# AntennaBoard.net
KiCad netlist of a schematic drawn in EAGLE
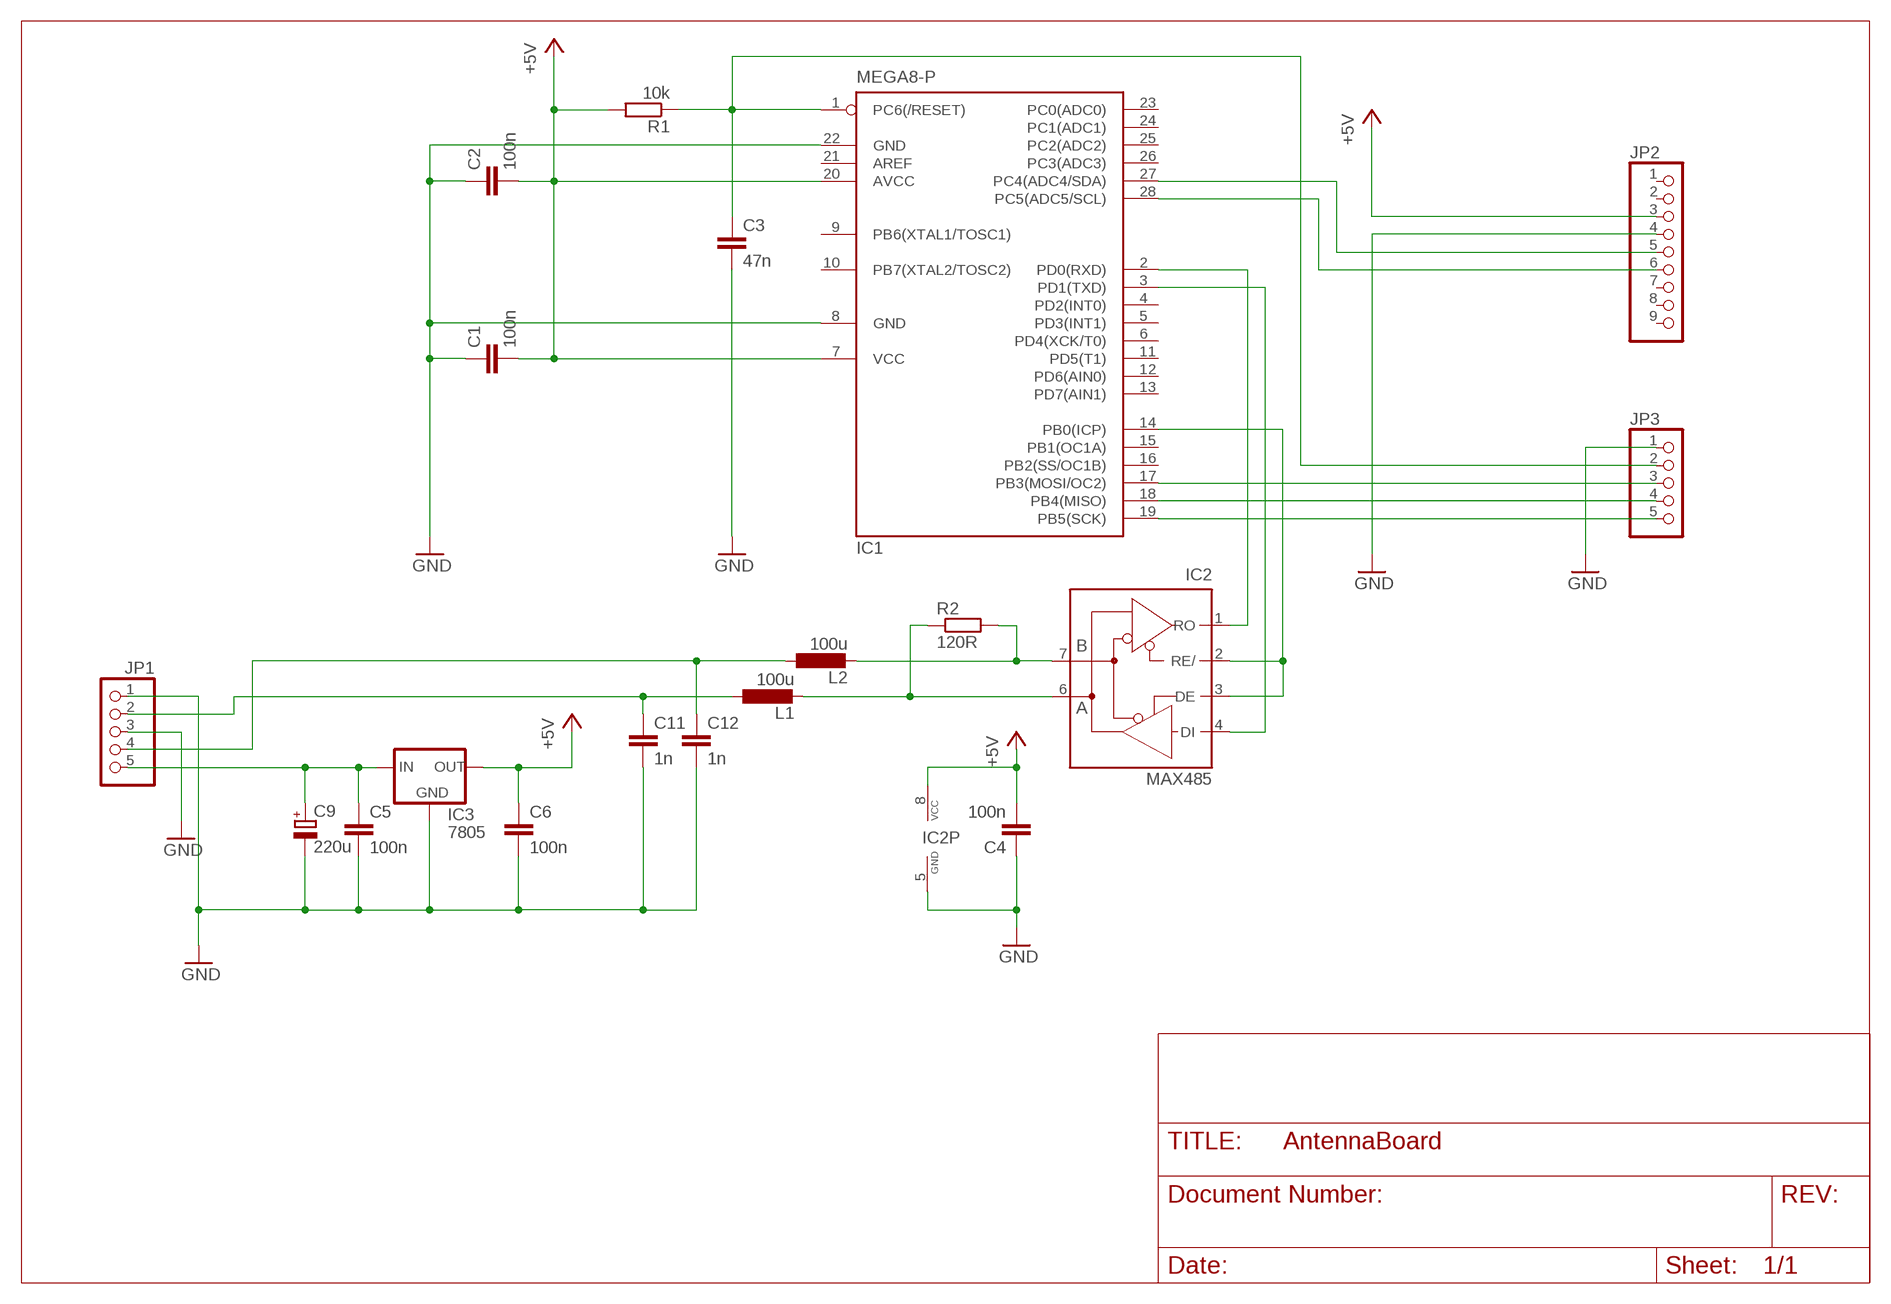
[diagram p0: schematic, sheet 1]

(export (version "E")
  (design (tool "Eeschema 10.0.6"))
  (components
    (comp (ref "C1")
      (value "100n")
      (footprint "eagle-import:C050-024X044")
      (libsource (lib "eagle-import") (part "C-EU050-024X044"))
    )
    (comp (ref "C2")
      (value "100n")
      (footprint "eagle-import:C050-024X044")
      (libsource (lib "eagle-import") (part "C-EU050-024X044"))
    )
    (comp (ref "C3")
      (value "47n")
      (footprint "eagle-import:C050-024X044")
      (libsource (lib "eagle-import") (part "C-EU050-024X044"))
    )
    (comp (ref "C4")
      (value "100n")
      (footprint "eagle-import:C050-024X044")
      (libsource (lib "eagle-import") (part "C-EU050-024X044"))
    )
    (comp (ref "C5")
      (value "100n")
      (footprint "eagle-import:C050-024X044")
      (libsource (lib "eagle-import") (part "C-EU050-024X044"))
    )
    (comp (ref "C6")
      (value "100n")
      (footprint "eagle-import:C050-024X044")
      (libsource (lib "eagle-import") (part "C-EU050-024X044"))
    )
    (comp (ref "C9")
      (value "220u")
      (footprint "eagle-import:E5-10,5")
      (libsource (lib "eagle-import") (part "CPOL-EUE5-10.5"))
    )
    (comp (ref "C11")
      (value "1n")
      (footprint "eagle-import:C025-024X044")
      (libsource (lib "eagle-import") (part "C-EU025-024X044"))
    )
    (comp (ref "C12")
      (value "1n")
      (footprint "eagle-import:C025-024X044")
      (libsource (lib "eagle-import") (part "C-EU025-024X044"))
    )
    (comp (ref "IC1")
      (value "MEGA8-P")
      (footprint "eagle-import:DIL28-3")
      (libsource (lib "eagle-import") (part "MEGA8-P"))
    )
    (comp (ref "IC2")
      (value "MAX485")
      (footprint "eagle-import:DIL08")
      (fields (field (name "MPN") "MAX481CPA+"))
      (libsource (lib "eagle-import") (part "MAX481CPA"))
    )
    (comp (ref "IC3")
      (value "7805")
      (footprint "eagle-import:78XXL")
      (libsource (lib "eagle-import") (part "78XXL"))
    )
    (comp (ref "JP1")
      (value "PINHD-1X5/90")
      (footprint "eagle-import:1X05_90")
      (libsource (lib "eagle-import") (part "PINHD-1X5/90"))
    )
    (comp (ref "JP2")
      (value "PINHD-1X9")
      (footprint "eagle-import:1X09")
      (libsource (lib "eagle-import") (part "PINHD-1X9"))
    )
    (comp (ref "JP3")
      (value "PINHD-1X5")
      (footprint "eagle-import:1X05")
      (libsource (lib "eagle-import") (part "PINHD-1X5"))
    )
    (comp (ref "L1")
      (value "100u")
      (footprint "eagle-import:0207_12")
      (libsource (lib "eagle-import") (part "L-EU0207/12"))
    )
    (comp (ref "L2")
      (value "100u")
      (footprint "eagle-import:0207_12")
      (libsource (lib "eagle-import") (part "L-EU0207/12"))
    )
    (comp (ref "R1")
      (value "10k")
      (footprint "eagle-import:0207_10")
      (libsource (lib "eagle-import") (part "R-EU_0207/10"))
    )
    (comp (ref "R2")
      (value "120R")
      (footprint "eagle-import:0207_10")
      (libsource (lib "eagle-import") (part "R-EU_0207/10"))
    )
  )
  (nets
    (net (code "1") (name "+5V") (class "Default")
      (node (ref "C1") (pin "2") (pinfunction "2_2") (pintype "passive"))
      (node (ref "C2") (pin "2") (pinfunction "2_2") (pintype "passive"))
      (node (ref "C4") (pin "2") (pinfunction "2_2") (pintype "passive"))
      (node (ref "C6") (pin "1") (pinfunction "1_1") (pintype "passive"))
      (node (ref "IC1") (pin "20") (pinfunction "AVCC_20") (pintype "power_in"))
      (node (ref "IC1") (pin "7") (pinfunction "VCC_7") (pintype "power_in"))
      (node (ref "IC2") (pin "8") (pinfunction "VCC_8") (pintype "power_in"))
      (node (ref "IC3") (pin "OUT") (pinfunction "OUT_OUT") (pintype "passive"))
      (node (ref "JP2") (pin "3") (pinfunction "3_3") (pintype "passive"))
      (node (ref "R1") (pin "2") (pinfunction "2_2") (pintype "passive"))
    )
    (net (code "2") (name "GND") (class "Default")
      (node (ref "C1") (pin "1") (pinfunction "1_1") (pintype "passive"))
      (node (ref "C11") (pin "2") (pinfunction "2_2") (pintype "passive"))
      (node (ref "C12") (pin "2") (pinfunction "2_2") (pintype "passive"))
      (node (ref "C2") (pin "1") (pinfunction "1_1") (pintype "passive"))
      (node (ref "C3") (pin "2") (pinfunction "2_2") (pintype "passive"))
      (node (ref "C4") (pin "1") (pinfunction "1_1") (pintype "passive"))
      (node (ref "C5") (pin "2") (pinfunction "2_2") (pintype "passive"))
      (node (ref "C6") (pin "2") (pinfunction "2_2") (pintype "passive"))
      (node (ref "C9") (pin "-") (pinfunction "-_-") (pintype "passive"))
      (node (ref "IC1") (pin "22") (pinfunction "GND_22") (pintype "power_in"))
      (node (ref "IC1") (pin "8") (pinfunction "GND_8") (pintype "power_in"))
      (node (ref "IC2") (pin "5") (pinfunction "GND_5") (pintype "power_in"))
      (node (ref "IC3") (pin "GND") (pinfunction "GND_GND") (pintype "input"))
      (node (ref "JP1") (pin "1") (pinfunction "1_1") (pintype "passive"))
      (node (ref "JP1") (pin "3") (pinfunction "3_3") (pintype "passive"))
      (node (ref "JP2") (pin "4") (pinfunction "4_4") (pintype "passive"))
      (node (ref "JP3") (pin "1") (pinfunction "1_1") (pintype "passive"))
    )
    (net (code "3") (name "Net-(C5-Pad1)") (class "Default")
      (node (ref "C5") (pin "1") (pinfunction "1_1") (pintype "passive"))
      (node (ref "C9") (pin "+") (pinfunction "+_+") (pintype "passive"))
      (node (ref "IC3") (pin "IN") (pinfunction "IN_IN") (pintype "input"))
      (node (ref "JP1") (pin "5") (pinfunction "5_5") (pintype "passive"))
    )
    (net (code "4") (name "Net-(C11-Pad1)") (class "Default")
      (node (ref "C11") (pin "1") (pinfunction "1_1") (pintype "passive"))
      (node (ref "JP1") (pin "2") (pinfunction "2_2") (pintype "passive"))
      (node (ref "L1") (pin "1") (pinfunction "1_1") (pintype "passive"))
    )
    (net (code "5") (name "Net-(C12-Pad1)") (class "Default")
      (node (ref "C12") (pin "1") (pinfunction "1_1") (pintype "passive"))
      (node (ref "JP1") (pin "4") (pinfunction "4_4") (pintype "passive"))
      (node (ref "L2") (pin "1") (pinfunction "1_1") (pintype "passive"))
    )
    (net (code "6") (name "Net-(IC1-PB0(ICP))") (class "Default")
      (node (ref "IC1") (pin "14") (pinfunction "PB0(ICP)_14") (pintype "bidirectional"))
      (node (ref "IC2") (pin "2") (pinfunction "RE/_2") (pintype "input"))
      (node (ref "IC2") (pin "3") (pinfunction "DE_3") (pintype "input"))
    )
    (net (code "7") (name "Net-(IC1-PB3(MOSI{slash}OC2))") (class "Default")
      (node (ref "IC1") (pin "17") (pinfunction "PB3(MOSI/OC2)_17") (pintype "bidirectional"))
      (node (ref "JP3") (pin "3") (pinfunction "3_3") (pintype "passive"))
    )
    (net (code "8") (name "Net-(IC1-PB4(MISO))") (class "Default")
      (node (ref "IC1") (pin "18") (pinfunction "PB4(MISO)_18") (pintype "bidirectional"))
      (node (ref "JP3") (pin "4") (pinfunction "4_4") (pintype "passive"))
    )
    (net (code "9") (name "Net-(IC1-PB5(SCK))") (class "Default")
      (node (ref "IC1") (pin "19") (pinfunction "PB5(SCK)_19") (pintype "bidirectional"))
      (node (ref "JP3") (pin "5") (pinfunction "5_5") (pintype "passive"))
    )
    (net (code "10") (name "Net-(IC1-PC4(ADC4{slash}SDA))") (class "Default")
      (node (ref "IC1") (pin "27") (pinfunction "PC4(ADC4/SDA)_27") (pintype "bidirectional"))
      (node (ref "JP2") (pin "5") (pinfunction "5_5") (pintype "passive"))
    )
    (net (code "11") (name "Net-(IC1-PC5(ADC5{slash}SCL))") (class "Default")
      (node (ref "IC1") (pin "28") (pinfunction "PC5(ADC5/SCL)_28") (pintype "bidirectional"))
      (node (ref "JP2") (pin "6") (pinfunction "6_6") (pintype "passive"))
    )
    (net (code "12") (name "Net-(IC1-PC6({slash}RESET))") (class "Default")
      (node (ref "C3") (pin "1") (pinfunction "1_1") (pintype "passive"))
      (node (ref "IC1") (pin "1") (pinfunction "PC6(/RESET)_1") (pintype "bidirectional"))
      (node (ref "JP3") (pin "2") (pinfunction "2_2") (pintype "passive"))
      (node (ref "R1") (pin "1") (pinfunction "1_1") (pintype "passive"))
    )
    (net (code "13") (name "Net-(IC1-PD0(RXD))") (class "Default")
      (node (ref "IC1") (pin "2") (pinfunction "PD0(RXD)_2") (pintype "bidirectional"))
      (node (ref "IC2") (pin "1") (pinfunction "RO_1") (pintype "output"))
    )
    (net (code "14") (name "Net-(IC1-PD1(TXD))") (class "Default")
      (node (ref "IC1") (pin "3") (pinfunction "PD1(TXD)_3") (pintype "bidirectional"))
      (node (ref "IC2") (pin "4") (pinfunction "DI_4") (pintype "input"))
    )
    (net (code "15") (name "Net-(IC2A-A)") (class "Default")
      (node (ref "IC2") (pin "6") (pinfunction "A_6") (pintype "passive"))
      (node (ref "L1") (pin "2") (pinfunction "2_2") (pintype "passive"))
      (node (ref "R2") (pin "1") (pinfunction "1_1") (pintype "passive"))
    )
    (net (code "16") (name "Net-(IC2A-B)") (class "Default")
      (node (ref "IC2") (pin "7") (pinfunction "B_7") (pintype "passive"))
      (node (ref "L2") (pin "2") (pinfunction "2_2") (pintype "passive"))
      (node (ref "R2") (pin "2") (pinfunction "2_2") (pintype "passive"))
    )
    (net (code "17") (name "unconnected-(IC1-AREF-Pad21)") (class "Default")
      (node (ref "IC1") (pin "21") (pinfunction "AREF_21") (pintype "passive"))
    )
    (net (code "18") (name "unconnected-(IC1-PB1(OC1A)-Pad15)") (class "Default")
      (node (ref "IC1") (pin "15") (pinfunction "PB1(OC1A)_15") (pintype "bidirectional"))
    )
    (net (code "19") (name "unconnected-(IC1-PB2(SS{slash}OC1B)-Pad16)") (class "Default")
      (node (ref "IC1") (pin "16") (pinfunction "PB2(SS/OC1B)_16") (pintype "bidirectional"))
    )
    (net (code "20") (name "unconnected-(IC1-PB6(XTAL1{slash}TOSC1)-Pad9)") (class "Default")
      (node (ref "IC1") (pin "9") (pinfunction "PB6(XTAL1/TOSC1)_9") (pintype "bidirectional"))
    )
    (net (code "21") (name "unconnected-(IC1-PB7(XTAL2{slash}TOSC2)-Pad10)") (class "Default")
      (node (ref "IC1") (pin "10") (pinfunction "PB7(XTAL2/TOSC2)_10") (pintype "bidirectional"))
    )
    (net (code "22") (name "unconnected-(IC1-PC0(ADC0)-Pad23)") (class "Default")
      (node (ref "IC1") (pin "23") (pinfunction "PC0(ADC0)_23") (pintype "bidirectional"))
    )
    (net (code "23") (name "unconnected-(IC1-PC1(ADC1)-Pad24)") (class "Default")
      (node (ref "IC1") (pin "24") (pinfunction "PC1(ADC1)_24") (pintype "bidirectional"))
    )
    (net (code "24") (name "unconnected-(IC1-PC2(ADC2)-Pad25)") (class "Default")
      (node (ref "IC1") (pin "25") (pinfunction "PC2(ADC2)_25") (pintype "bidirectional"))
    )
    (net (code "25") (name "unconnected-(IC1-PC3(ADC3)-Pad26)") (class "Default")
      (node (ref "IC1") (pin "26") (pinfunction "PC3(ADC3)_26") (pintype "bidirectional"))
    )
    (net (code "26") (name "unconnected-(IC1-PD2(INT0)-Pad4)") (class "Default")
      (node (ref "IC1") (pin "4") (pinfunction "PD2(INT0)_4") (pintype "bidirectional"))
    )
    (net (code "27") (name "unconnected-(IC1-PD3(INT1)-Pad5)") (class "Default")
      (node (ref "IC1") (pin "5") (pinfunction "PD3(INT1)_5") (pintype "bidirectional"))
    )
    (net (code "28") (name "unconnected-(IC1-PD4(XCK{slash}T0)-Pad6)") (class "Default")
      (node (ref "IC1") (pin "6") (pinfunction "PD4(XCK/T0)_6") (pintype "bidirectional"))
    )
    (net (code "29") (name "unconnected-(IC1-PD5(T1)-Pad11)") (class "Default")
      (node (ref "IC1") (pin "11") (pinfunction "PD5(T1)_11") (pintype "bidirectional"))
    )
    (net (code "30") (name "unconnected-(IC1-PD6(AIN0)-Pad12)") (class "Default")
      (node (ref "IC1") (pin "12") (pinfunction "PD6(AIN0)_12") (pintype "bidirectional"))
    )
    (net (code "31") (name "unconnected-(IC1-PD7(AIN1)-Pad13)") (class "Default")
      (node (ref "IC1") (pin "13") (pinfunction "PD7(AIN1)_13") (pintype "bidirectional"))
    )
    (net (code "32") (name "unconnected-(JP2-Pad1)") (class "Default")
      (node (ref "JP2") (pin "1") (pinfunction "1_1") (pintype "passive"))
    )
    (net (code "33") (name "unconnected-(JP2-Pad2)") (class "Default")
      (node (ref "JP2") (pin "2") (pinfunction "2_2") (pintype "passive"))
    )
    (net (code "34") (name "unconnected-(JP2-Pad7)") (class "Default")
      (node (ref "JP2") (pin "7") (pinfunction "7_7") (pintype "passive"))
    )
    (net (code "35") (name "unconnected-(JP2-Pad8)") (class "Default")
      (node (ref "JP2") (pin "8") (pinfunction "8_8") (pintype "passive"))
    )
    (net (code "36") (name "unconnected-(JP2-Pad9)") (class "Default")
      (node (ref "JP2") (pin "9") (pinfunction "9_9") (pintype "passive"))
    )
  )
)
